# CPU_DDR2.net
KiCad netlist of a schematic drawn in Altium Designer
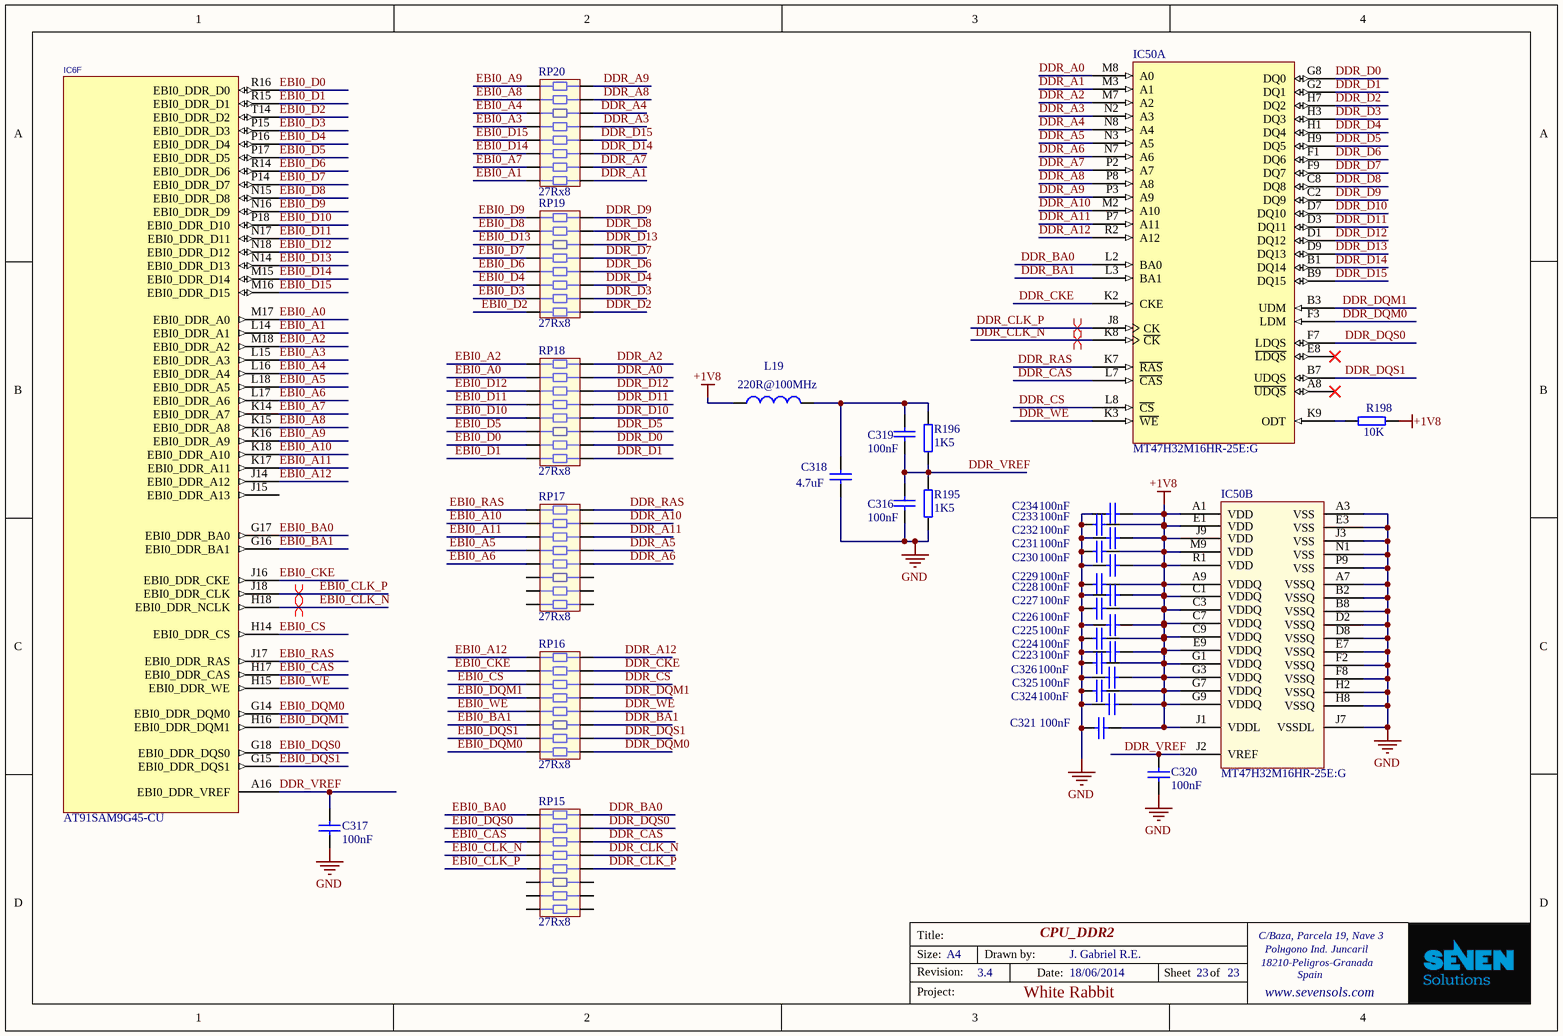
[diagram p0: CPU_DDR2.SchDoc]

(export (version "E")
  (design (tool "Eeschema 10.0.6"))
  (components
    (comp (ref "C223")
      (value "100nF")
      (footprint "CC1005-0402")
      (description "Capacitor")
      (fields
        (field (name "TOLERANCE") "±10%")
        (field (name "VOLTAGE") "16V")
        (field (name "PUBLISHER") "Altium Limited")
      )
      (libsource (lib "wr_switch") (part "Cap"))
    )
    (comp (ref "C224")
      (value "100nF")
      (footprint "CC1005-0402")
      (description "Capacitor")
      (fields
        (field (name "TOLERANCE") "±10%")
        (field (name "VOLTAGE") "16V")
        (field (name "PUBLISHER") "Altium Limited")
      )
      (libsource (lib "wr_switch") (part "Cap"))
    )
    (comp (ref "C225")
      (value "100nF")
      (footprint "CC1005-0402")
      (description "Capacitor")
      (fields
        (field (name "TOLERANCE") "±10%")
        (field (name "VOLTAGE") "16V")
        (field (name "PUBLISHER") "Altium Limited")
      )
      (libsource (lib "wr_switch") (part "Cap"))
    )
    (comp (ref "C226")
      (value "100nF")
      (footprint "CC1005-0402")
      (description "Capacitor")
      (fields
        (field (name "TOLERANCE") "±10%")
        (field (name "VOLTAGE") "16V")
        (field (name "PUBLISHER") "Altium Limited")
      )
      (libsource (lib "wr_switch") (part "Cap"))
    )
    (comp (ref "C227")
      (value "100nF")
      (footprint "CC1005-0402")
      (description "Capacitor")
      (fields
        (field (name "TOLERANCE") "±10%")
        (field (name "VOLTAGE") "16V")
        (field (name "PUBLISHER") "Altium Limited")
      )
      (libsource (lib "wr_switch") (part "Cap"))
    )
    (comp (ref "C228")
      (value "100nF")
      (footprint "CC1005-0402")
      (description "Capacitor")
      (fields
        (field (name "TOLERANCE") "±10%")
        (field (name "VOLTAGE") "16V")
        (field (name "PUBLISHER") "Altium Limited")
      )
      (libsource (lib "wr_switch") (part "Cap"))
    )
    (comp (ref "C229")
      (value "100nF")
      (footprint "CC1005-0402")
      (description "Capacitor")
      (fields
        (field (name "TOLERANCE") "±10%")
        (field (name "VOLTAGE") "16V")
        (field (name "PUBLISHER") "Altium Limited")
      )
      (libsource (lib "wr_switch") (part "Cap"))
    )
    (comp (ref "C230")
      (value "100nF")
      (footprint "CC1005-0402")
      (description "Capacitor")
      (fields
        (field (name "TOLERANCE") "±10%")
        (field (name "VOLTAGE") "16V")
        (field (name "PUBLISHER") "Altium Limited")
      )
      (libsource (lib "wr_switch") (part "Cap"))
    )
    (comp (ref "C231")
      (value "100nF")
      (footprint "CC1005-0402")
      (description "Capacitor")
      (fields
        (field (name "TOLERANCE") "±10%")
        (field (name "VOLTAGE") "16V")
        (field (name "PUBLISHER") "Altium Limited")
      )
      (libsource (lib "wr_switch") (part "Cap"))
    )
    (comp (ref "C232")
      (value "100nF")
      (footprint "CC1005-0402")
      (description "Capacitor")
      (fields
        (field (name "TOLERANCE") "±10%")
        (field (name "VOLTAGE") "16V")
        (field (name "PUBLISHER") "Altium Limited")
      )
      (libsource (lib "wr_switch") (part "Cap"))
    )
    (comp (ref "C233")
      (value "100nF")
      (footprint "CC1005-0402")
      (description "Capacitor")
      (fields
        (field (name "TOLERANCE") "±10%")
        (field (name "VOLTAGE") "16V")
        (field (name "PUBLISHER") "Altium Limited")
      )
      (libsource (lib "wr_switch") (part "Cap"))
    )
    (comp (ref "C234")
      (value "100nF")
      (footprint "CC1005-0402")
      (description "Capacitor")
      (fields
        (field (name "TOLERANCE") "±10%")
        (field (name "VOLTAGE") "16V")
        (field (name "PUBLISHER") "Altium Limited")
      )
      (libsource (lib "wr_switch") (part "Cap"))
    )
    (comp (ref "C316")
      (value "100nF")
      (footprint "CC1005-0402")
      (description "Capacitor")
      (fields
        (field (name "TOLERANCE") "±10%")
        (field (name "VOLTAGE") "16V")
        (field (name "PUBLISHER") "Altium Limited")
      )
      (libsource (lib "wr_switch") (part "Cap"))
    )
    (comp (ref "C317")
      (value "100nF")
      (footprint "CC1005-0402")
      (description "Capacitor")
      (fields
        (field (name "TOLERANCE") "±10%")
        (field (name "VOLTAGE") "16V")
        (field (name "PUBLISHER") "Altium Limited")
      )
      (libsource (lib "wr_switch") (part "Cap"))
    )
    (comp (ref "C318")
      (value "4.7uF")
      (footprint "CC1608-0603")
      (description "Capacitor")
      (fields
        (field (name "TOLERANCE") "±10%")
        (field (name "VOLTAGE") "10V")
        (field (name "PUBLISHER") "Altium Limited")
      )
      (libsource (lib "wr_switch") (part "Cap"))
    )
    (comp (ref "C319")
      (value "100nF")
      (footprint "CC1005-0402")
      (description "Capacitor")
      (fields
        (field (name "TOLERANCE") "±10%")
        (field (name "VOLTAGE") "16V")
        (field (name "PUBLISHER") "Altium Limited")
      )
      (libsource (lib "wr_switch") (part "Cap"))
    )
    (comp (ref "C320")
      (value "100nF")
      (footprint "CC1005-0402")
      (description "Capacitor")
      (fields
        (field (name "TOLERANCE") "±10%")
        (field (name "VOLTAGE") "16V")
        (field (name "PUBLISHER") "Altium Limited")
      )
      (libsource (lib "wr_switch") (part "Cap"))
    )
    (comp (ref "C321")
      (value "100nF")
      (footprint "CC1005-0402")
      (description "Capacitor")
      (fields
        (field (name "TOLERANCE") "±10%")
        (field (name "VOLTAGE") "16V")
        (field (name "PUBLISHER") "Altium Limited")
      )
      (libsource (lib "wr_switch") (part "Cap"))
    )
    (comp (ref "C324")
      (value "100nF")
      (footprint "CC1005-0402")
      (description "Capacitor")
      (fields
        (field (name "TOLERANCE") "±10%")
        (field (name "VOLTAGE") "16V")
        (field (name "PUBLISHER") "Altium Limited")
      )
      (libsource (lib "wr_switch") (part "Cap"))
    )
    (comp (ref "C325")
      (value "100nF")
      (footprint "CC1005-0402")
      (description "Capacitor")
      (fields
        (field (name "TOLERANCE") "±10%")
        (field (name "VOLTAGE") "16V")
        (field (name "PUBLISHER") "Altium Limited")
      )
      (libsource (lib "wr_switch") (part "Cap"))
    )
    (comp (ref "C326")
      (value "100nF")
      (footprint "CC1005-0402")
      (description "Capacitor")
      (fields
        (field (name "TOLERANCE") "±10%")
        (field (name "VOLTAGE") "16V")
        (field (name "PUBLISHER") "Altium Limited")
      )
      (libsource (lib "wr_switch") (part "Cap"))
    )
    (comp (ref "IC6")
      (value "AT91SAM9G45-CU")
      (footprint "TFBGA324")
      (description "Atmel 400MHz ARM926 MCU")
      (libsource (lib "wr_switch") (part "AT91SAM9G45-CU"))
    )
    (comp (ref "IC50")
      (value "MT47H32M16HR-25E:G")
      (footprint "7S_WR:BGA90C80P9X15_1250X800X120")
      (description "DDR2 SDRAM 8Mx16x4 Banks")
      (libsource (lib "wr_switch") (part "MT47H32M16"))
    )
    (comp (ref "L19")
      (value "220R@100MHz Ferrite Bead")
      (footprint "0603")
      (description "ferrite bead")
      (fields (field (name "IMPEDANCE") "220R@100MHz"))
      (libsource (lib "wr_switch") (part "L_FERRITE_BEAD"))
    )
    (comp (ref "R195")
      (value "1K5")
      (footprint "0402")
      (description "SMD Resistor")
      (fields (field (name "TOLERANCE") "±1%"))
      (libsource (lib "wr_switch") (part "RES_SMD"))
    )
    (comp (ref "R196")
      (value "1K5")
      (footprint "0402")
      (description "SMD Resistor")
      (fields (field (name "TOLERANCE") "±1%"))
      (libsource (lib "wr_switch") (part "RES_SMD"))
    )
    (comp (ref "R198")
      (value "10K")
      (footprint "0402")
      (description "SMD Resistor")
      (fields (field (name "TOLERANCE") "±1%"))
      (libsource (lib "wr_switch") (part "RES_SMD"))
    )
    (comp (ref "RP15")
      (value "27Rx8")
      (footprint "RESCAXS50P160X380X60-16N")
      (description "27R, 62.5mW Chip Resistor 8 Elements Array")
      (fields (field (name "TOLERANCE") "±5%") (field (name "Comment") "27R x 8"))
      (libsource (lib "wr_switch") (part "RES_8xARRAY"))
    )
    (comp (ref "RP16")
      (value "27Rx8")
      (footprint "RESCAXS50P160X380X60-16N")
      (description "27R, 62.5mW Chip Resistor 8 Elements Array")
      (fields (field (name "TOLERANCE") "±5%") (field (name "Comment") "27R x 8"))
      (libsource (lib "wr_switch") (part "RES_8xARRAY"))
    )
    (comp (ref "RP17")
      (value "27Rx8")
      (footprint "RESCAXS50P160X380X60-16N")
      (description "27R, 62.5mW Chip Resistor 8 Elements Array")
      (fields (field (name "TOLERANCE") "±5%") (field (name "Comment") "27R x 8"))
      (libsource (lib "wr_switch") (part "RES_8xARRAY"))
    )
    (comp (ref "RP18")
      (value "27Rx8")
      (footprint "RESCAXS50P160X380X60-16N")
      (description "27R, 62.5mW Chip Resistor 8 Elements Array")
      (fields (field (name "TOLERANCE") "±5%") (field (name "Comment") "27R x 8"))
      (libsource (lib "wr_switch") (part "RES_8xARRAY"))
    )
    (comp (ref "RP19")
      (value "27Rx8")
      (footprint "RESCAXS50P160X380X60-16N")
      (description "27R, 62.5mW Chip Resistor 8 Elements Array")
      (fields (field (name "TOLERANCE") "±5%") (field (name "Comment") "27R x 8"))
      (libsource (lib "") (part "RES_8xARRAY_1"))
    )
    (comp (ref "RP20")
      (value "27Rx8")
      (footprint "RESCAXS50P160X380X60-16N")
      (description "27R, 62.5mW Chip Resistor 8 Elements Array")
      (fields (field (name "TOLERANCE") "±5%") (field (name "Comment") "27R x 8"))
      (libsource (lib "") (part "RES_8xARRAY_1"))
    )
  )
  (nets
    (net (code "1") (name "+1V8") (class "Default")
      (node (ref "C223") (pin "1") (pinfunction "1_1") (pintype "passive"))
      (node (ref "C224") (pin "1") (pinfunction "1_1") (pintype "passive"))
      (node (ref "C225") (pin "1") (pinfunction "1_1") (pintype "passive"))
      (node (ref "C226") (pin "1") (pinfunction "1_1") (pintype "passive"))
      (node (ref "C227") (pin "1") (pinfunction "1_1") (pintype "passive"))
      (node (ref "C228") (pin "1") (pinfunction "1_1") (pintype "passive"))
      (node (ref "C229") (pin "1") (pinfunction "1_1") (pintype "passive"))
      (node (ref "C230") (pin "1") (pinfunction "1_1") (pintype "passive"))
      (node (ref "C231") (pin "1") (pinfunction "1_1") (pintype "passive"))
      (node (ref "C232") (pin "1") (pinfunction "1_1") (pintype "passive"))
      (node (ref "C233") (pin "1") (pinfunction "1_1") (pintype "passive"))
      (node (ref "C234") (pin "1") (pinfunction "1_1") (pintype "passive"))
      (node (ref "C321") (pin "1") (pinfunction "1_1") (pintype "passive"))
      (node (ref "C324") (pin "1") (pinfunction "1_1") (pintype "passive"))
      (node (ref "C325") (pin "1") (pinfunction "1_1") (pintype "passive"))
      (node (ref "C326") (pin "1") (pinfunction "1_1") (pintype "passive"))
      (node (ref "IC50") (pin "A1") (pinfunction "VDD_A1") (pintype "power_in"))
      (node (ref "IC50") (pin "A9") (pinfunction "VDDQ_A9") (pintype "power_in"))
      (node (ref "IC50") (pin "C1") (pinfunction "VDDQ_C1") (pintype "power_in"))
      (node (ref "IC50") (pin "C3") (pinfunction "VDDQ_C3") (pintype "power_in"))
      (node (ref "IC50") (pin "C7") (pinfunction "VDDQ_C7") (pintype "power_in"))
      (node (ref "IC50") (pin "C9") (pinfunction "VDDQ_C9") (pintype "power_in"))
      (node (ref "IC50") (pin "E1") (pinfunction "VDD_E1") (pintype "power_in"))
      (node (ref "IC50") (pin "E9") (pinfunction "VDDQ_E9") (pintype "power_in"))
      (node (ref "IC50") (pin "G1") (pinfunction "VDDQ_G1") (pintype "power_in"))
      (node (ref "IC50") (pin "G3") (pinfunction "VDDQ_G3") (pintype "power_in"))
      (node (ref "IC50") (pin "G7") (pinfunction "VDDQ_G7") (pintype "power_in"))
      (node (ref "IC50") (pin "G9") (pinfunction "VDDQ_G9") (pintype "power_in"))
      (node (ref "IC50") (pin "J1") (pinfunction "VDDL_J1") (pintype "power_in"))
      (node (ref "IC50") (pin "J9") (pinfunction "VDD_J9") (pintype "power_in"))
      (node (ref "IC50") (pin "M9") (pinfunction "VDD_M9") (pintype "power_in"))
      (node (ref "IC50") (pin "R1") (pinfunction "VDD_R1") (pintype "power_in"))
      (node (ref "L19") (pin "1") (pinfunction "1_1") (pintype "passive"))
      (node (ref "R198") (pin "1") (pinfunction "1_1") (pintype "passive"))
    )
    (net (code "2") (name "/DDR_A0") (class "Default")
      (node (ref "IC50") (pin "M8") (pinfunction "A0_M8") (pintype "input"))
      (node (ref "RP18") (pin "15") (pinfunction "15_15") (pintype "passive"))
    )
    (net (code "3") (name "/DDR_A1") (class "Default")
      (node (ref "IC50") (pin "M3") (pinfunction "A1_M3") (pintype "input"))
      (node (ref "RP20") (pin "16") (pinfunction "16_16") (pintype "passive"))
    )
    (net (code "4") (name "/DDR_A2") (class "Default")
      (node (ref "IC50") (pin "M7") (pinfunction "A2_M7") (pintype "input"))
      (node (ref "RP18") (pin "16") (pinfunction "16_16") (pintype "passive"))
    )
    (net (code "5") (name "/DDR_A3") (class "Default")
      (node (ref "IC50") (pin "N2") (pinfunction "A3_N2") (pintype "input"))
      (node (ref "RP20") (pin "12") (pinfunction "12_12") (pintype "passive"))
    )
    (net (code "6") (name "/DDR_A4") (class "Default")
      (node (ref "IC50") (pin "N8") (pinfunction "A4_N8") (pintype "input"))
      (node (ref "RP20") (pin "11") (pinfunction "11_11") (pintype "passive"))
    )
    (net (code "7") (name "/DDR_A5") (class "Default")
      (node (ref "IC50") (pin "N3") (pinfunction "A5_N3") (pintype "input"))
      (node (ref "RP17") (pin "13") (pinfunction "13_13") (pintype "passive"))
    )
    (net (code "8") (name "/DDR_A6") (class "Default")
      (node (ref "IC50") (pin "N7") (pinfunction "A6_N7") (pintype "input"))
      (node (ref "RP17") (pin "12") (pinfunction "12_12") (pintype "passive"))
    )
    (net (code "9") (name "/DDR_A7") (class "Default")
      (node (ref "IC50") (pin "P2") (pinfunction "A7_P2") (pintype "input"))
      (node (ref "RP20") (pin "15") (pinfunction "15_15") (pintype "passive"))
    )
    (net (code "10") (name "/DDR_A8") (class "Default")
      (node (ref "IC50") (pin "P8") (pinfunction "A8_P8") (pintype "input"))
      (node (ref "RP20") (pin "10") (pinfunction "10_10") (pintype "passive"))
    )
    (net (code "11") (name "/DDR_A9") (class "Default")
      (node (ref "IC50") (pin "P3") (pinfunction "A9_P3") (pintype "input"))
      (node (ref "RP20") (pin "9") (pinfunction "9_9") (pintype "passive"))
    )
    (net (code "12") (name "/DDR_A10") (class "Default")
      (node (ref "IC50") (pin "M2") (pinfunction "A10_M2") (pintype "input"))
      (node (ref "RP17") (pin "15") (pinfunction "15_15") (pintype "passive"))
    )
    (net (code "13") (name "/DDR_A11") (class "Default")
      (node (ref "IC50") (pin "P7") (pinfunction "A11_P7") (pintype "input"))
      (node (ref "RP17") (pin "14") (pinfunction "14_14") (pintype "passive"))
    )
    (net (code "14") (name "/DDR_A12") (class "Default")
      (node (ref "IC50") (pin "R2") (pinfunction "A12_R2") (pintype "input"))
      (node (ref "RP16") (pin "16") (pinfunction "16_16") (pintype "passive"))
    )
    (net (code "15") (name "/DDR_BA0") (class "Default")
      (node (ref "IC50") (pin "L2") (pinfunction "BA0_L2") (pintype "input"))
      (node (ref "RP15") (pin "16") (pinfunction "16_16") (pintype "passive"))
    )
    (net (code "16") (name "/DDR_BA1") (class "Default")
      (node (ref "IC50") (pin "L3") (pinfunction "BA1_L3") (pintype "input"))
      (node (ref "RP16") (pin "11") (pinfunction "11_11") (pintype "passive"))
    )
    (net (code "17") (name "/DDR_CAS") (class "Default")
      (node (ref "IC50") (pin "L7") (pinfunction "~{CAS}_L7") (pintype "input"))
      (node (ref "RP15") (pin "14") (pinfunction "14_14") (pintype "passive"))
    )
    (net (code "18") (name "/DDR_CKE") (class "Default")
      (node (ref "IC50") (pin "K2") (pinfunction "CKE_K2") (pintype "input"))
      (node (ref "RP16") (pin "15") (pinfunction "15_15") (pintype "passive"))
    )
    (net (code "19") (name "/DDR_CLK_N") (class "Default")
      (node (ref "IC50") (pin "K8") (pinfunction "~{CK}_K8") (pintype "input"))
      (node (ref "RP15") (pin "13") (pinfunction "13_13") (pintype "passive"))
    )
    (net (code "20") (name "/DDR_CLK_P") (class "Default")
      (node (ref "IC50") (pin "J8") (pinfunction "CK_J8") (pintype "input"))
      (node (ref "RP15") (pin "12") (pinfunction "12_12") (pintype "passive"))
    )
    (net (code "21") (name "/DDR_CS") (class "Default")
      (node (ref "IC50") (pin "L8") (pinfunction "~{CS}_L8") (pintype "input"))
      (node (ref "RP16") (pin "14") (pinfunction "14_14") (pintype "passive"))
    )
    (net (code "22") (name "/DDR_D0") (class "Default")
      (node (ref "IC50") (pin "G8") (pinfunction "DQ0_G8") (pintype "bidirectional"))
      (node (ref "RP18") (pin "10") (pinfunction "10_10") (pintype "passive"))
    )
    (net (code "23") (name "/DDR_D1") (class "Default")
      (node (ref "IC50") (pin "G2") (pinfunction "DQ1_G2") (pintype "bidirectional"))
      (node (ref "RP18") (pin "9") (pinfunction "9_9") (pintype "passive"))
    )
    (net (code "24") (name "/DDR_D2") (class "Default")
      (node (ref "IC50") (pin "H7") (pinfunction "DQ2_H7") (pintype "bidirectional"))
      (node (ref "RP19") (pin "16") (pinfunction "16_16") (pintype "passive"))
    )
    (net (code "25") (name "/DDR_D3") (class "Default")
      (node (ref "IC50") (pin "H3") (pinfunction "DQ3_H3") (pintype "bidirectional"))
      (node (ref "RP19") (pin "15") (pinfunction "15_15") (pintype "passive"))
    )
    (net (code "26") (name "/DDR_D4") (class "Default")
      (node (ref "IC50") (pin "H1") (pinfunction "DQ4_H1") (pintype "bidirectional"))
      (node (ref "RP19") (pin "14") (pinfunction "14_14") (pintype "passive"))
    )
    (net (code "27") (name "/DDR_D5") (class "Default")
      (node (ref "IC50") (pin "H9") (pinfunction "DQ5_H9") (pintype "bidirectional"))
      (node (ref "RP18") (pin "11") (pinfunction "11_11") (pintype "passive"))
    )
    (net (code "28") (name "/DDR_D6") (class "Default")
      (node (ref "IC50") (pin "F1") (pinfunction "DQ6_F1") (pintype "bidirectional"))
      (node (ref "RP19") (pin "13") (pinfunction "13_13") (pintype "passive"))
    )
    (net (code "29") (name "/DDR_D7") (class "Default")
      (node (ref "IC50") (pin "F9") (pinfunction "DQ7_F9") (pintype "bidirectional"))
      (node (ref "RP19") (pin "12") (pinfunction "12_12") (pintype "passive"))
    )
    (net (code "30") (name "/DDR_D8") (class "Default")
      (node (ref "IC50") (pin "C8") (pinfunction "DQ8_C8") (pintype "bidirectional"))
      (node (ref "RP19") (pin "10") (pinfunction "10_10") (pintype "passive"))
    )
    (net (code "31") (name "/DDR_D9") (class "Default")
      (node (ref "IC50") (pin "C2") (pinfunction "DQ9_C2") (pintype "bidirectional"))
      (node (ref "RP19") (pin "9") (pinfunction "9_9") (pintype "passive"))
    )
    (net (code "32") (name "/DDR_D10") (class "Default")
      (node (ref "IC50") (pin "D7") (pinfunction "DQ10_D7") (pintype "bidirectional"))
      (node (ref "RP18") (pin "12") (pinfunction "12_12") (pintype "passive"))
    )
    (net (code "33") (name "/DDR_D11") (class "Default")
      (node (ref "IC50") (pin "D3") (pinfunction "DQ11_D3") (pintype "bidirectional"))
      (node (ref "RP18") (pin "13") (pinfunction "13_13") (pintype "passive"))
    )
    (net (code "34") (name "/DDR_D12") (class "Default")
      (node (ref "IC50") (pin "D1") (pinfunction "DQ12_D1") (pintype "bidirectional"))
      (node (ref "RP18") (pin "14") (pinfunction "14_14") (pintype "passive"))
    )
    (net (code "35") (name "/DDR_D13") (class "Default")
      (node (ref "IC50") (pin "D9") (pinfunction "DQ13_D9") (pintype "bidirectional"))
      (node (ref "RP19") (pin "11") (pinfunction "11_11") (pintype "passive"))
    )
    (net (code "36") (name "/DDR_D14") (class "Default")
      (node (ref "IC50") (pin "B1") (pinfunction "DQ14_B1") (pintype "bidirectional"))
      (node (ref "RP20") (pin "14") (pinfunction "14_14") (pintype "passive"))
    )
    (net (code "37") (name "/DDR_D15") (class "Default")
      (node (ref "IC50") (pin "B9") (pinfunction "DQ15_B9") (pintype "bidirectional"))
      (node (ref "RP20") (pin "13") (pinfunction "13_13") (pintype "passive"))
    )
    (net (code "38") (name "/DDR_DQM0") (class "Default")
      (node (ref "IC50") (pin "F3") (pinfunction "LDM_F3") (pintype "input"))
      (node (ref "RP16") (pin "9") (pinfunction "9_9") (pintype "passive"))
    )
    (net (code "39") (name "/DDR_DQM1") (class "Default")
      (node (ref "IC50") (pin "B3") (pinfunction "UDM_B3") (pintype "input"))
      (node (ref "RP16") (pin "13") (pinfunction "13_13") (pintype "passive"))
    )
    (net (code "40") (name "/DDR_DQS0") (class "Default")
      (node (ref "IC50") (pin "F7") (pinfunction "LDQS_F7") (pintype "bidirectional"))
      (node (ref "RP15") (pin "15") (pinfunction "15_15") (pintype "passive"))
    )
    (net (code "41") (name "/DDR_DQS1") (class "Default")
      (node (ref "IC50") (pin "B7") (pinfunction "UDQS_B7") (pintype "bidirectional"))
      (node (ref "RP16") (pin "10") (pinfunction "10_10") (pintype "passive"))
    )
    (net (code "42") (name "/DDR_RAS") (class "Default")
      (node (ref "IC50") (pin "K7") (pinfunction "~{RAS}_K7") (pintype "input"))
      (node (ref "RP17") (pin "16") (pinfunction "16_16") (pintype "passive"))
    )
    (net (code "43") (name "/DDR_VREF") (class "Default")
      (node (ref "C316") (pin "1") (pinfunction "1_1") (pintype "passive"))
      (node (ref "C317") (pin "1") (pinfunction "1_1") (pintype "passive"))
      (node (ref "C319") (pin "2") (pinfunction "2_2") (pintype "passive"))
      (node (ref "C320") (pin "1") (pinfunction "1_1") (pintype "passive"))
      (node (ref "IC50") (pin "J2") (pinfunction "VREF_J2") (pintype "power_in"))
      (node (ref "IC6") (pin "A16") (pinfunction "EBI0_DDR_VREF_A16") (pintype "passive"))
      (node (ref "R195") (pin "2") (pinfunction "2_2") (pintype "passive"))
      (node (ref "R196") (pin "1") (pinfunction "1_1") (pintype "passive"))
    )
    (net (code "44") (name "/DDR_WE") (class "Default")
      (node (ref "IC50") (pin "K3") (pinfunction "~{WE}_K3") (pintype "input"))
      (node (ref "RP16") (pin "12") (pinfunction "12_12") (pintype "passive"))
    )
    (net (code "45") (name "/EBI0_A0") (class "Default")
      (node (ref "IC6") (pin "M17") (pinfunction "EBI0_DDR_A0_M17") (pintype "output"))
      (node (ref "RP18") (pin "2") (pinfunction "2_2") (pintype "passive"))
    )
    (net (code "46") (name "/EBI0_A1") (class "Default")
      (node (ref "IC6") (pin "L14") (pinfunction "EBI0_DDR_A1_L14") (pintype "output"))
      (node (ref "RP20") (pin "1") (pinfunction "1_1") (pintype "passive"))
    )
    (net (code "47") (name "/EBI0_A2") (class "Default")
      (node (ref "IC6") (pin "M18") (pinfunction "EBI0_DDR_A2_M18") (pintype "output"))
      (node (ref "RP18") (pin "1") (pinfunction "1_1") (pintype "passive"))
    )
    (net (code "48") (name "/EBI0_A3") (class "Default")
      (node (ref "IC6") (pin "L15") (pinfunction "EBI0_DDR_A3_L15") (pintype "output"))
      (node (ref "RP20") (pin "5") (pinfunction "5_5") (pintype "passive"))
    )
    (net (code "49") (name "/EBI0_A4") (class "Default")
      (node (ref "IC6") (pin "L16") (pinfunction "EBI0_DDR_A4_L16") (pintype "output"))
      (node (ref "RP20") (pin "6") (pinfunction "6_6") (pintype "passive"))
    )
    (net (code "50") (name "/EBI0_A5") (class "Default")
      (node (ref "IC6") (pin "L18") (pinfunction "EBI0_DDR_A5_L18") (pintype "output"))
      (node (ref "RP17") (pin "4") (pinfunction "4_4") (pintype "passive"))
    )
    (net (code "51") (name "/EBI0_A6") (class "Default")
      (node (ref "IC6") (pin "L17") (pinfunction "EBI0_DDR_A6_L17") (pintype "output"))
      (node (ref "RP17") (pin "5") (pinfunction "5_5") (pintype "passive"))
    )
    (net (code "52") (name "/EBI0_A7") (class "Default")
      (node (ref "IC6") (pin "K14") (pinfunction "EBI0_DDR_A7_K14") (pintype "output"))
      (node (ref "RP20") (pin "2") (pinfunction "2_2") (pintype "passive"))
    )
    (net (code "53") (name "/EBI0_A8") (class "Default")
      (node (ref "IC6") (pin "K15") (pinfunction "EBI0_DDR_A8_K15") (pintype "output"))
      (node (ref "RP20") (pin "7") (pinfunction "7_7") (pintype "passive"))
    )
    (net (code "54") (name "/EBI0_A9") (class "Default")
      (node (ref "IC6") (pin "K16") (pinfunction "EBI0_DDR_A9_K16") (pintype "output"))
      (node (ref "RP20") (pin "8") (pinfunction "8_8") (pintype "passive"))
    )
    (net (code "55") (name "/EBI0_A10") (class "Default")
      (node (ref "IC6") (pin "K18") (pinfunction "EBI0_DDR_A10_K18") (pintype "output"))
      (node (ref "RP17") (pin "2") (pinfunction "2_2") (pintype "passive"))
    )
    (net (code "56") (name "/EBI0_A11") (class "Default")
      (node (ref "IC6") (pin "K17") (pinfunction "EBI0_DDR_A11_K17") (pintype "output"))
      (node (ref "RP17") (pin "3") (pinfunction "3_3") (pintype "passive"))
    )
    (net (code "57") (name "/EBI0_A12") (class "Default")
      (node (ref "IC6") (pin "J14") (pinfunction "EBI0_DDR_A12_J14") (pintype "output"))
      (node (ref "RP16") (pin "1") (pinfunction "1_1") (pintype "passive"))
    )
    (net (code "58") (name "/EBI0_BA0") (class "Default")
      (node (ref "IC6") (pin "G17") (pinfunction "EBI0_DDR_BA0_G17") (pintype "output"))
      (node (ref "RP15") (pin "1") (pinfunction "1_1") (pintype "passive"))
    )
    (net (code "59") (name "/EBI0_BA1") (class "Default")
      (node (ref "IC6") (pin "G16") (pinfunction "EBI0_DDR_BA1_G16") (pintype "output"))
      (node (ref "RP16") (pin "6") (pinfunction "6_6") (pintype "passive"))
    )
    (net (code "60") (name "/EBI0_CAS") (class "Default")
      (node (ref "IC6") (pin "H17") (pinfunction "EBI0_DDR_CAS_H17") (pintype "output"))
      (node (ref "RP15") (pin "3") (pinfunction "3_3") (pintype "passive"))
    )
    (net (code "61") (name "/EBI0_CKE") (class "Default")
      (node (ref "IC6") (pin "J16") (pinfunction "EBI0_DDR_CKE_J16") (pintype "output"))
      (node (ref "RP16") (pin "2") (pinfunction "2_2") (pintype "passive"))
    )
    (net (code "62") (name "/EBI0_CLK_N") (class "Default")
      (node (ref "IC6") (pin "H18") (pinfunction "EBI0_DDR_NCLK_H18") (pintype "output"))
      (node (ref "RP15") (pin "4") (pinfunction "4_4") (pintype "passive"))
    )
    (net (code "63") (name "/EBI0_CLK_P") (class "Default")
      (node (ref "IC6") (pin "J18") (pinfunction "EBI0_DDR_CLK_J18") (pintype "output"))
      (node (ref "RP15") (pin "5") (pinfunction "5_5") (pintype "passive"))
    )
    (net (code "64") (name "/EBI0_CS") (class "Default")
      (node (ref "IC6") (pin "H14") (pinfunction "EBI0_DDR_CS_H14") (pintype "output"))
      (node (ref "RP16") (pin "3") (pinfunction "3_3") (pintype "passive"))
    )
    (net (code "65") (name "/EBI0_D0") (class "Default")
      (node (ref "IC6") (pin "R16") (pinfunction "EBI0_DDR_D0_R16") (pintype "bidirectional"))
      (node (ref "RP18") (pin "7") (pinfunction "7_7") (pintype "passive"))
    )
    (net (code "66") (name "/EBI0_D1") (class "Default")
      (node (ref "IC6") (pin "R15") (pinfunction "EBI0_DDR_D1_R15") (pintype "bidirectional"))
      (node (ref "RP18") (pin "8") (pinfunction "8_8") (pintype "passive"))
    )
    (net (code "67") (name "/EBI0_D2") (class "Default")
      (node (ref "IC6") (pin "T14") (pinfunction "EBI0_DDR_D2_T14") (pintype "bidirectional"))
      (node (ref "RP19") (pin "1") (pinfunction "1_1") (pintype "passive"))
    )
    (net (code "68") (name "/EBI0_D3") (class "Default")
      (node (ref "IC6") (pin "P15") (pinfunction "EBI0_DDR_D3_P15") (pintype "bidirectional"))
      (node (ref "RP19") (pin "2") (pinfunction "2_2") (pintype "passive"))
    )
    (net (code "69") (name "/EBI0_D4") (class "Default")
      (node (ref "IC6") (pin "P16") (pinfunction "EBI0_DDR_D4_P16") (pintype "bidirectional"))
      (node (ref "RP19") (pin "3") (pinfunction "3_3") (pintype "passive"))
    )
    (net (code "70") (name "/EBI0_D5") (class "Default")
      (node (ref "IC6") (pin "P17") (pinfunction "EBI0_DDR_D5_P17") (pintype "bidirectional"))
      (node (ref "RP18") (pin "6") (pinfunction "6_6") (pintype "passive"))
    )
    (net (code "71") (name "/EBI0_D6") (class "Default")
      (node (ref "IC6") (pin "R14") (pinfunction "EBI0_DDR_D6_R14") (pintype "bidirectional"))
      (node (ref "RP19") (pin "4") (pinfunction "4_4") (pintype "passive"))
    )
    (net (code "72") (name "/EBI0_D7") (class "Default")
      (node (ref "IC6") (pin "P14") (pinfunction "EBI0_DDR_D7_P14") (pintype "bidirectional"))
      (node (ref "RP19") (pin "5") (pinfunction "5_5") (pintype "passive"))
    )
    (net (code "73") (name "/EBI0_D8") (class "Default")
      (node (ref "IC6") (pin "N15") (pinfunction "EBI0_DDR_D8_N15") (pintype "bidirectional"))
      (node (ref "RP19") (pin "7") (pinfunction "7_7") (pintype "passive"))
    )
    (net (code "74") (name "/EBI0_D9") (class "Default")
      (node (ref "IC6") (pin "N16") (pinfunction "EBI0_DDR_D9_N16") (pintype "bidirectional"))
      (node (ref "RP19") (pin "8") (pinfunction "8_8") (pintype "passive"))
    )
    (net (code "75") (name "/EBI0_D10") (class "Default")
      (node (ref "IC6") (pin "P18") (pinfunction "EBI0_DDR_D10_P18") (pintype "bidirectional"))
      (node (ref "RP18") (pin "5") (pinfunction "5_5") (pintype "passive"))
    )
    (net (code "76") (name "/EBI0_D11") (class "Default")
      (node (ref "IC6") (pin "N17") (pinfunction "EBI0_DDR_D11_N17") (pintype "bidirectional"))
      (node (ref "RP18") (pin "4") (pinfunction "4_4") (pintype "passive"))
    )
    (net (code "77") (name "/EBI0_D12") (class "Default")
      (node (ref "IC6") (pin "N18") (pinfunction "EBI0_DDR_D12_N18") (pintype "bidirectional"))
      (node (ref "RP18") (pin "3") (pinfunction "3_3") (pintype "passive"))
    )
    (net (code "78") (name "/EBI0_D13") (class "Default")
      (node (ref "IC6") (pin "N14") (pinfunction "EBI0_DDR_D13_N14") (pintype "bidirectional"))
      (node (ref "RP19") (pin "6") (pinfunction "6_6") (pintype "passive"))
    )
    (net (code "79") (name "/EBI0_D14") (class "Default")
      (node (ref "IC6") (pin "M15") (pinfunction "EBI0_DDR_D14_M15") (pintype "bidirectional"))
      (node (ref "RP20") (pin "3") (pinfunction "3_3") (pintype "passive"))
    )
    (net (code "80") (name "/EBI0_D15") (class "Default")
      (node (ref "IC6") (pin "M16") (pinfunction "EBI0_DDR_D15_M16") (pintype "bidirectional"))
      (node (ref "RP20") (pin "4") (pinfunction "4_4") (pintype "passive"))
    )
    (net (code "81") (name "/EBI0_DQM0") (class "Default")
      (node (ref "IC6") (pin "G14") (pinfunction "EBI0_DDR_DQM0_G14") (pintype "output"))
      (node (ref "RP16") (pin "8") (pinfunction "8_8") (pintype "passive"))
    )
    (net (code "82") (name "/EBI0_DQM1") (class "Default")
      (node (ref "IC6") (pin "H16") (pinfunction "EBI0_DDR_DQM1_H16") (pintype "output"))
      (node (ref "RP16") (pin "4") (pinfunction "4_4") (pintype "passive"))
    )
    (net (code "83") (name "/EBI0_DQS0") (class "Default")
      (node (ref "IC6") (pin "G18") (pinfunction "EBI0_DDR_DQS0_G18") (pintype "output"))
      (node (ref "RP15") (pin "2") (pinfunction "2_2") (pintype "passive"))
    )
    (net (code "84") (name "/EBI0_DQS1") (class "Default")
      (node (ref "IC6") (pin "G15") (pinfunction "EBI0_DDR_DQS1_G15") (pintype "output"))
      (node (ref "RP16") (pin "7") (pinfunction "7_7") (pintype "passive"))
    )
    (net (code "85") (name "/EBI0_RAS") (class "Default")
      (node (ref "IC6") (pin "J17") (pinfunction "EBI0_DDR_RAS_J17") (pintype "output"))
      (node (ref "RP17") (pin "1") (pinfunction "1_1") (pintype "passive"))
    )
    (net (code "86") (name "/EBI0_WE") (class "Default")
      (node (ref "IC6") (pin "H15") (pinfunction "EBI0_DDR_WE_H15") (pintype "output"))
      (node (ref "RP16") (pin "5") (pinfunction "5_5") (pintype "passive"))
    )
    (net (code "87") (name "GND") (class "Default")
      (node (ref "C223") (pin "2") (pinfunction "2_2") (pintype "passive"))
      (node (ref "C224") (pin "2") (pinfunction "2_2") (pintype "passive"))
      (node (ref "C225") (pin "2") (pinfunction "2_2") (pintype "passive"))
      (node (ref "C226") (pin "2") (pinfunction "2_2") (pintype "passive"))
      (node (ref "C227") (pin "2") (pinfunction "2_2") (pintype "passive"))
      (node (ref "C228") (pin "2") (pinfunction "2_2") (pintype "passive"))
      (node (ref "C229") (pin "2") (pinfunction "2_2") (pintype "passive"))
      (node (ref "C230") (pin "2") (pinfunction "2_2") (pintype "passive"))
      (node (ref "C231") (pin "2") (pinfunction "2_2") (pintype "passive"))
      (node (ref "C232") (pin "2") (pinfunction "2_2") (pintype "passive"))
      (node (ref "C233") (pin "2") (pinfunction "2_2") (pintype "passive"))
      (node (ref "C234") (pin "2") (pinfunction "2_2") (pintype "passive"))
      (node (ref "C316") (pin "2") (pinfunction "2_2") (pintype "passive"))
      (node (ref "C317") (pin "2") (pinfunction "2_2") (pintype "passive"))
      (node (ref "C318") (pin "1") (pinfunction "1_1") (pintype "passive"))
      (node (ref "C320") (pin "2") (pinfunction "2_2") (pintype "passive"))
      (node (ref "C321") (pin "2") (pinfunction "2_2") (pintype "passive"))
      (node (ref "C324") (pin "2") (pinfunction "2_2") (pintype "passive"))
      (node (ref "C325") (pin "2") (pinfunction "2_2") (pintype "passive"))
      (node (ref "C326") (pin "2") (pinfunction "2_2") (pintype "passive"))
      (node (ref "IC50") (pin "A3") (pinfunction "VSS_A3") (pintype "power_in"))
      (node (ref "IC50") (pin "A7") (pinfunction "VSSQ_A7") (pintype "power_in"))
      (node (ref "IC50") (pin "B2") (pinfunction "VSSQ_B2") (pintype "power_in"))
      (node (ref "IC50") (pin "B8") (pinfunction "VSSQ_B8") (pintype "power_in"))
      (node (ref "IC50") (pin "D2") (pinfunction "VSSQ_D2") (pintype "power_in"))
      (node (ref "IC50") (pin "D8") (pinfunction "VSSQ_D8") (pintype "power_in"))
      (node (ref "IC50") (pin "E3") (pinfunction "VSS_E3") (pintype "power_in"))
      (node (ref "IC50") (pin "E7") (pinfunction "VSSQ_E7") (pintype "power_in"))
      (node (ref "IC50") (pin "F2") (pinfunction "VSSQ_F2") (pintype "power_in"))
      (node (ref "IC50") (pin "F8") (pinfunction "VSSQ_F8") (pintype "power_in"))
      (node (ref "IC50") (pin "H2") (pinfunction "VSSQ_H2") (pintype "power_in"))
      (node (ref "IC50") (pin "H8") (pinfunction "VSSQ_H8") (pintype "power_in"))
      (node (ref "IC50") (pin "J3") (pinfunction "VSS_J3") (pintype "power_in"))
      (node (ref "IC50") (pin "J7") (pinfunction "VSSDL_J7") (pintype "power_in"))
      (node (ref "IC50") (pin "N1") (pinfunction "VSS_N1") (pintype "power_in"))
      (node (ref "IC50") (pin "P9") (pinfunction "VSS_P9") (pintype "power_in"))
      (node (ref "R195") (pin "1") (pinfunction "1_1") (pintype "passive"))
    )
    (net (code "88") (name "Net-(C318-Pad2)") (class "Default")
      (node (ref "C318") (pin "2") (pinfunction "2_2") (pintype "passive"))
      (node (ref "C319") (pin "1") (pinfunction "1_1") (pintype "passive"))
      (node (ref "L19") (pin "2") (pinfunction "2_2") (pintype "passive"))
      (node (ref "R196") (pin "2") (pinfunction "2_2") (pintype "passive"))
    )
    (net (code "89") (name "Net-(IC50A-ODT)") (class "Default")
      (node (ref "IC50") (pin "K9") (pinfunction "ODT_K9") (pintype "input"))
      (node (ref "R198") (pin "2") (pinfunction "2_2") (pintype "passive"))
    )
    (net (code "90") (name "unconnected-(IC6F-EBI0_DDR_A13-PadJ15)") (class "Default")
      (node (ref "IC6") (pin "J15") (pinfunction "EBI0_DDR_A13_J15") (pintype "output"))
    )
    (net (code "91") (name "unconnected-(IC50A-~{LDQS}-PadE8)") (class "Default")
      (node (ref "IC50") (pin "E8") (pinfunction "~{LDQS}_E8") (pintype "bidirectional+no_connect"))
    )
    (net (code "92") (name "unconnected-(IC50A-~{UDQS}-PadA8)") (class "Default")
      (node (ref "IC50") (pin "A8") (pinfunction "~{UDQS}_A8") (pintype "bidirectional+no_connect"))
    )
    (net (code "93") (name "unconnected-(RP15-Pad6)") (class "Default")
      (node (ref "RP15") (pin "6") (pinfunction "6_6") (pintype "passive"))
    )
    (net (code "94") (name "unconnected-(RP15-Pad7)") (class "Default")
      (node (ref "RP15") (pin "7") (pinfunction "7_7") (pintype "passive"))
    )
    (net (code "95") (name "unconnected-(RP15-Pad8)") (class "Default")
      (node (ref "RP15") (pin "8") (pinfunction "8_8") (pintype "passive"))
    )
    (net (code "96") (name "unconnected-(RP15-Pad9)") (class "Default")
      (node (ref "RP15") (pin "9") (pinfunction "9_9") (pintype "passive"))
    )
    (net (code "97") (name "unconnected-(RP15-Pad10)") (class "Default")
      (node (ref "RP15") (pin "10") (pinfunction "10_10") (pintype "passive"))
    )
    (net (code "98") (name "unconnected-(RP15-Pad11)") (class "Default")
      (node (ref "RP15") (pin "11") (pinfunction "11_11") (pintype "passive"))
    )
    (net (code "99") (name "unconnected-(RP17-Pad6)") (class "Default")
      (node (ref "RP17") (pin "6") (pinfunction "6_6") (pintype "passive"))
    )
    (net (code "100") (name "unconnected-(RP17-Pad7)") (class "Default")
      (node (ref "RP17") (pin "7") (pinfunction "7_7") (pintype "passive"))
    )
    (net (code "101") (name "unconnected-(RP17-Pad8)") (class "Default")
      (node (ref "RP17") (pin "8") (pinfunction "8_8") (pintype "passive"))
    )
    (net (code "102") (name "unconnected-(RP17-Pad9)") (class "Default")
      (node (ref "RP17") (pin "9") (pinfunction "9_9") (pintype "passive"))
    )
    (net (code "103") (name "unconnected-(RP17-Pad10)") (class "Default")
      (node (ref "RP17") (pin "10") (pinfunction "10_10") (pintype "passive"))
    )
    (net (code "104") (name "unconnected-(RP17-Pad11)") (class "Default")
      (node (ref "RP17") (pin "11") (pinfunction "11_11") (pintype "passive"))
    )
  )
)
